# main_v2_0.net
KiCad netlist of a schematic drawn in EAGLE
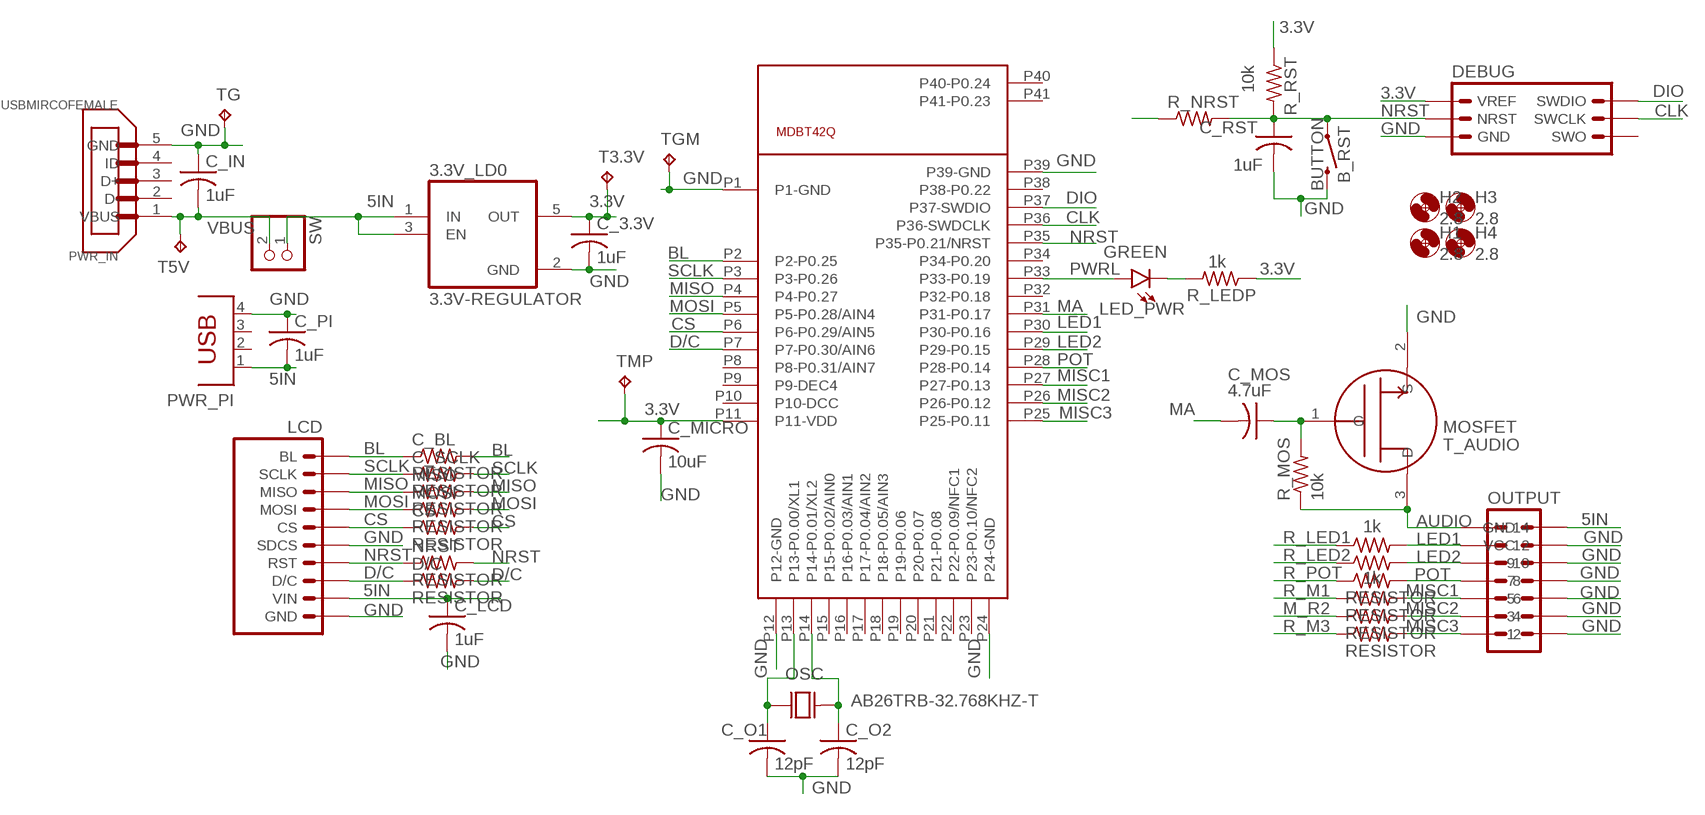
[diagram p0: schematic, sheet 1]

(export (version "E")
  (design (tool "Eeschema 10.0.6"))
  (components
    (comp (ref "3.3V_LD0")
      (value "3.3V-REGULATOR")
      (footprint "eagle-import:SOT95P280X145-5N")
      (fields (field (name "MF") "Texas Instruments") (field (name "MP") "TLV75533PDBVR"))
      (libsource (lib "eagle-import") (part "3.3V-REGULATOR"))
    )
    (comp (ref "B_RST")
      (value "BUTTON")
      (footprint "eagle-import:TACTILE_SWITCH_SMD_6.2MM_TALL")
      (libsource (lib "eagle-import") (part "BUTTON"))
    )
    (comp (ref "CS")
      (value "RESISTOR")
      (footprint "eagle-import:R0805")
      (libsource (lib "eagle-import") (part "RESISTOR"))
    )
    (comp (ref "C_3.3V")
      (value "1uF")
      (footprint "eagle-import:C0805")
      (libsource (lib "eagle-import") (part "CAP"))
    )
    (comp (ref "C_BL")
      (value "RESISTOR")
      (footprint "eagle-import:R0805")
      (libsource (lib "eagle-import") (part "RESISTOR"))
    )
    (comp (ref "C_IN")
      (value "1uF")
      (footprint "eagle-import:C0805")
      (libsource (lib "eagle-import") (part "CAP"))
    )
    (comp (ref "C_LCD")
      (value "1uF")
      (footprint "eagle-import:C0805")
      (libsource (lib "eagle-import") (part "CAP"))
    )
    (comp (ref "C_MICRO")
      (value "10uF")
      (footprint "eagle-import:C0805")
      (libsource (lib "eagle-import") (part "CAP"))
    )
    (comp (ref "C_MOS")
      (value "4.7uF")
      (footprint "eagle-import:C0805")
      (libsource (lib "eagle-import") (part "CAP"))
    )
    (comp (ref "C_O1")
      (value "12pF")
      (footprint "eagle-import:C0805")
      (libsource (lib "eagle-import") (part "CAP"))
    )
    (comp (ref "C_O2")
      (value "12pF")
      (footprint "eagle-import:C0805")
      (libsource (lib "eagle-import") (part "CAP"))
    )
    (comp (ref "C_PI")
      (value "1uF")
      (footprint "eagle-import:C0805")
      (libsource (lib "eagle-import") (part "CAP"))
    )
    (comp (ref "C_RST")
      (value "1uF")
      (footprint "eagle-import:C0805")
      (libsource (lib "eagle-import") (part "CAP"))
    )
    (comp (ref "C_SCLK")
      (value "RESISTOR")
      (footprint "eagle-import:R0805")
      (libsource (lib "eagle-import") (part "RESISTOR"))
    )
    (comp (ref "D/C")
      (value "RESISTOR")
      (footprint "eagle-import:R0805")
      (libsource (lib "eagle-import") (part "RESISTOR"))
    )
    (comp (ref "DEBUG")
      (value "DEBUGGER")
      (footprint "eagle-import:MA03-2")
      (libsource (lib "eagle-import") (part "DEBUGGER"))
    )
    (comp (ref "H1")
      (value "2.8")
      (footprint "eagle-import:2,8")
      (libsource (lib "eagle-import") (part "MOUNT-HOLE2.8"))
    )
    (comp (ref "H2")
      (value "2.8")
      (footprint "eagle-import:2,8")
      (libsource (lib "eagle-import") (part "MOUNT-HOLE2.8"))
    )
    (comp (ref "H3")
      (value "2.8")
      (footprint "eagle-import:2,8")
      (libsource (lib "eagle-import") (part "MOUNT-HOLE2.8"))
    )
    (comp (ref "H4")
      (value "2.8")
      (footprint "eagle-import:2,8")
      (libsource (lib "eagle-import") (part "MOUNT-HOLE2.8"))
    )
    (comp (ref "LCD")
      (value "LCDHEADERS")
      (footprint "eagle-import:MA10-1")
      (libsource (lib "eagle-import") (part "LCDHEADERS"))
    )
    (comp (ref "LED_PWR")
      (value "GREEN")
      (footprint "eagle-import:LED-1206")
      (libsource (lib "eagle-import") (part "LED-GREENLILYPAD"))
    )
    (comp (ref "MISO")
      (value "RESISTOR")
      (footprint "eagle-import:R0805")
      (libsource (lib "eagle-import") (part "RESISTOR"))
    )
    (comp (ref "MOSI")
      (value "RESISTOR")
      (footprint "eagle-import:R0805")
      (libsource (lib "eagle-import") (part "RESISTOR"))
    )
    (comp (ref "M_R2")
      (value "RESISTOR")
      (footprint "eagle-import:R0805")
      (libsource (lib "eagle-import") (part "RESISTOR"))
    )
    (comp (ref "NRST")
      (value "RESISTOR")
      (footprint "eagle-import:R0805")
      (libsource (lib "eagle-import") (part "RESISTOR"))
    )
    (comp (ref "OSC")
      (value "AB26TRB-32.768KHZ-T")
      (footprint "eagle-import:XTAL_AB26TRB-32.768KHZ-T")
      (fields (field (name "DIGI-KEY_PART_NUMBER") "535-9033-1-ND") (field (name "MF") "Abracon"))
      (libsource (lib "eagle-import") (part "AB26TRB-32.768KHZ-T"))
    )
    (comp (ref "OUTPUT")
      (value "OUTHEADER")
      (footprint "eagle-import:MA07-2")
      (libsource (lib "eagle-import") (part "OUTHEADER"))
    )
    (comp (ref "PWR_IN")
      (value "USBMIRCOFEMALE")
      (footprint "eagle-import:MOLEX_0473460001")
      (fields (field (name "MF") "Weidmuller") (field (name "MP") "0473460001"))
      (libsource (lib "eagle-import") (part "USBMIRCOFEMALE"))
    )
    (comp (ref "PWR_PI")
      (value "USBCON")
      (footprint "eagle-import:PN87520")
      (libsource (lib "eagle-import") (part "USBCON"))
    )
    (comp (ref "R_LED1")
      (value "1k")
      (footprint "eagle-import:R0805")
      (libsource (lib "eagle-import") (part "RESISTOR"))
    )
    (comp (ref "R_LED2")
      (value "1k")
      (footprint "eagle-import:R0805")
      (libsource (lib "eagle-import") (part "RESISTOR"))
    )
    (comp (ref "R_LEDP")
      (value "1k")
      (footprint "eagle-import:R0805")
      (libsource (lib "eagle-import") (part "RESISTOR"))
    )
    (comp (ref "R_M1")
      (value "RESISTOR")
      (footprint "eagle-import:R0805")
      (libsource (lib "eagle-import") (part "RESISTOR"))
    )
    (comp (ref "R_M3")
      (value "RESISTOR")
      (footprint "eagle-import:R0805")
      (libsource (lib "eagle-import") (part "RESISTOR"))
    )
    (comp (ref "R_MOS")
      (value "10k")
      (footprint "eagle-import:R0805")
      (libsource (lib "eagle-import") (part "RESISTOR"))
    )
    (comp (ref "R_NRST")
      (value "RESISTOR")
      (footprint "eagle-import:R0805")
      (libsource (lib "eagle-import") (part "RESISTOR"))
    )
    (comp (ref "R_POT")
      (value "RESISTOR")
      (footprint "eagle-import:R0805")
      (libsource (lib "eagle-import") (part "RESISTOR"))
    )
    (comp (ref "R_RST")
      (value "10k")
      (footprint "eagle-import:R0805")
      (libsource (lib "eagle-import") (part "RESISTOR"))
    )
    (comp (ref "SW")
      (value "PINHD-1X2")
      (footprint "eagle-import:1X02")
      (libsource (lib "eagle-import") (part "PINHD-1X2"))
    )
    (comp (ref "T3.3V")
      (value "TPTP11SQ")
      (footprint "eagle-import:TP11SQ")
      (libsource (lib "eagle-import") (part "TPTP11SQ"))
    )
    (comp (ref "T5V")
      (value "TPTP11SQ")
      (footprint "eagle-import:TP11SQ")
      (libsource (lib "eagle-import") (part "TPTP11SQ"))
    )
    (comp (ref "TG")
      (value "TPTP11SQ")
      (footprint "eagle-import:TP11SQ")
      (libsource (lib "eagle-import") (part "TPTP11SQ"))
    )
    (comp (ref "TGM")
      (value "TPTP11SQ")
      (footprint "eagle-import:TP11SQ")
      (libsource (lib "eagle-import") (part "TPTP11SQ"))
    )
    (comp (ref "TMP")
      (value "TPTP11SQ")
      (footprint "eagle-import:TP11SQ")
      (libsource (lib "eagle-import") (part "TPTP11SQ"))
    )
    (comp (ref "T_AUDIO")
      (value "MOSFET")
      (footprint "eagle-import:SOT23")
      (libsource (lib "eagle-import") (part "MOSFET"))
    )
    (comp (ref "U$1")
      (value "MDBT42Q")
      (footprint "eagle-import:MDBT40")
      (libsource (lib "eagle-import") (part "MDBT42Q"))
    )
  )
  (nets
    (net (code "1") (name "/3.3V") (class "Default")
      (node (ref "3.3V_LD0") (pin "5") (pinfunction "OUT_5") (pintype "output"))
      (node (ref "C_3.3V") (pin "1") (pinfunction "1_1") (pintype "passive"))
      (node (ref "C_MICRO") (pin "1") (pinfunction "1_1") (pintype "passive"))
      (node (ref "DEBUG") (pin "6") (pinfunction "VREF_6") (pintype "passive"))
      (node (ref "R_LEDP") (pin "1") (pinfunction "1_1") (pintype "passive"))
      (node (ref "R_RST") (pin "1") (pinfunction "1_1") (pintype "passive"))
      (node (ref "T3.3V") (pin "TP") (pinfunction "TP_TP") (pintype "input"))
      (node (ref "TMP") (pin "TP") (pinfunction "TP_TP") (pintype "input"))
      (node (ref "U$1") (pin "P11") (pinfunction "P11-VDD_P11") (pintype "bidirectional"))
    )
    (net (code "2") (name "/5IN") (class "Default")
      (node (ref "3.3V_LD0") (pin "1") (pinfunction "IN_1") (pintype "input"))
      (node (ref "3.3V_LD0") (pin "3") (pinfunction "EN_3") (pintype "input"))
      (node (ref "C_LCD") (pin "1") (pinfunction "1_1") (pintype "passive"))
      (node (ref "C_PI") (pin "2") (pinfunction "2_2") (pintype "passive"))
      (node (ref "LCD") (pin "2") (pinfunction "VIN_2") (pintype "passive"))
      (node (ref "OUTPUT") (pin "13") (pinfunction "GND_13") (pintype "passive"))
      (node (ref "PWR_PI") (pin "1") (pinfunction "1_1") (pintype "passive"))
      (node (ref "SW") (pin "1") (pinfunction "1_1") (pintype "passive"))
    )
    (net (code "3") (name "/AUDIO") (class "Default")
      (node (ref "OUTPUT") (pin "14") (pinfunction "14_14") (pintype "passive"))
      (node (ref "R_MOS") (pin "1") (pinfunction "1_1") (pintype "passive"))
      (node (ref "T_AUDIO") (pin "3") (pinfunction "D_3") (pintype "bidirectional"))
    )
    (net (code "4") (name "/BL") (class "Default")
      (node (ref "C_BL") (pin "1") (pinfunction "1_1") (pintype "passive"))
      (node (ref "C_BL") (pin "2") (pinfunction "2_2") (pintype "passive"))
      (node (ref "LCD") (pin "10") (pinfunction "BL_10") (pintype "passive"))
      (node (ref "U$1") (pin "P2") (pinfunction "P2-P0.25_P2") (pintype "bidirectional"))
    )
    (net (code "5") (name "/CLK") (class "Default")
      (node (ref "DEBUG") (pin "3") (pinfunction "SWCLK_3") (pintype "passive"))
      (node (ref "U$1") (pin "P36") (pinfunction "P36-SWDCLK_P36") (pintype "bidirectional"))
    )
    (net (code "6") (name "/CS") (class "Default")
      (node (ref "CS") (pin "1") (pinfunction "1_1") (pintype "passive"))
      (node (ref "CS") (pin "2") (pinfunction "2_2") (pintype "passive"))
      (node (ref "LCD") (pin "6") (pinfunction "CS_6") (pintype "passive"))
      (node (ref "U$1") (pin "P6") (pinfunction "P6-P0.29/AIN5_P6") (pintype "bidirectional"))
    )
    (net (code "7") (name "/DIO") (class "Default")
      (node (ref "DEBUG") (pin "5") (pinfunction "SWDIO_5") (pintype "passive"))
      (node (ref "U$1") (pin "P37") (pinfunction "P37-SWDIO_P37") (pintype "bidirectional"))
    )
    (net (code "8") (name "/D{slash}C") (class "Default")
      (node (ref "D/C") (pin "1") (pinfunction "1_1") (pintype "passive"))
      (node (ref "D/C") (pin "2") (pinfunction "2_2") (pintype "passive"))
      (node (ref "LCD") (pin "3") (pinfunction "D/C_3") (pintype "passive"))
      (node (ref "U$1") (pin "P7") (pinfunction "P7-P0.30/AIN6_P7") (pintype "bidirectional"))
    )
    (net (code "9") (name "/GND") (class "Default")
      (node (ref "3.3V_LD0") (pin "2") (pinfunction "GND_2") (pintype "power_in"))
      (node (ref "B_RST") (pin "B1") (pinfunction "2_B1") (pintype "passive"))
      (node (ref "B_RST") (pin "B2") (pinfunction "2_B2") (pintype "passive"))
      (node (ref "C_3.3V") (pin "2") (pinfunction "2_2") (pintype "passive"))
      (node (ref "C_IN") (pin "1") (pinfunction "1_1") (pintype "passive"))
      (node (ref "C_LCD") (pin "2") (pinfunction "2_2") (pintype "passive"))
      (node (ref "C_MICRO") (pin "2") (pinfunction "2_2") (pintype "passive"))
      (node (ref "C_O1") (pin "2") (pinfunction "2_2") (pintype "passive"))
      (node (ref "C_O2") (pin "2") (pinfunction "2_2") (pintype "passive"))
      (node (ref "C_PI") (pin "1") (pinfunction "1_1") (pintype "passive"))
      (node (ref "C_RST") (pin "2") (pinfunction "2_2") (pintype "passive"))
      (node (ref "DEBUG") (pin "2") (pinfunction "GND_2") (pintype "passive"))
      (node (ref "LCD") (pin "1") (pinfunction "GND_1") (pintype "passive"))
      (node (ref "LCD") (pin "5") (pinfunction "SDCS_5") (pintype "passive"))
      (node (ref "OUTPUT") (pin "1") (pinfunction "1_1") (pintype "passive"))
      (node (ref "OUTPUT") (pin "11") (pinfunction "VCC_11") (pintype "passive"))
      (node (ref "OUTPUT") (pin "3") (pinfunction "3_3") (pintype "passive"))
      (node (ref "OUTPUT") (pin "5") (pinfunction "5_5") (pintype "passive"))
      (node (ref "OUTPUT") (pin "7") (pinfunction "7_7") (pintype "passive"))
      (node (ref "OUTPUT") (pin "9") (pinfunction "9_9") (pintype "passive"))
      (node (ref "PWR_IN") (pin "5") (pinfunction "GND_5") (pintype "passive"))
      (node (ref "PWR_PI") (pin "4") (pinfunction "4_4") (pintype "passive"))
      (node (ref "TG") (pin "TP") (pinfunction "TP_TP") (pintype "input"))
      (node (ref "TGM") (pin "TP") (pinfunction "TP_TP") (pintype "input"))
      (node (ref "T_AUDIO") (pin "2") (pinfunction "S_2") (pintype "bidirectional"))
      (node (ref "U$1") (pin "P1") (pinfunction "P1-GND_P1") (pintype "bidirectional"))
      (node (ref "U$1") (pin "P12") (pinfunction "P12-GND_P12") (pintype "bidirectional"))
      (node (ref "U$1") (pin "P24") (pinfunction "P24-GND_P24") (pintype "bidirectional"))
      (node (ref "U$1") (pin "P39") (pinfunction "P39-GND_P39") (pintype "bidirectional"))
    )
    (net (code "10") (name "/LED1") (class "Default")
      (node (ref "OUTPUT") (pin "12") (pinfunction "12_12") (pintype "passive"))
      (node (ref "R_LED1") (pin "1") (pinfunction "1_1") (pintype "passive"))
      (node (ref "R_LED1") (pin "2") (pinfunction "2_2") (pintype "passive"))
      (node (ref "U$1") (pin "P30") (pinfunction "P30-P0.16_P30") (pintype "bidirectional"))
    )
    (net (code "11") (name "/LED2") (class "Default")
      (node (ref "OUTPUT") (pin "10") (pinfunction "10_10") (pintype "passive"))
      (node (ref "R_LED2") (pin "1") (pinfunction "1_1") (pintype "passive"))
      (node (ref "R_LED2") (pin "2") (pinfunction "2_2") (pintype "passive"))
      (node (ref "U$1") (pin "P29") (pinfunction "P29-P0.15_P29") (pintype "bidirectional"))
    )
    (net (code "12") (name "/MA") (class "Default")
      (node (ref "C_MOS") (pin "2") (pinfunction "2_2") (pintype "passive"))
      (node (ref "U$1") (pin "P31") (pinfunction "P31-P0.17_P31") (pintype "bidirectional"))
    )
    (net (code "13") (name "/MISC1") (class "Default")
      (node (ref "OUTPUT") (pin "6") (pinfunction "6_6") (pintype "passive"))
      (node (ref "R_M1") (pin "1") (pinfunction "1_1") (pintype "passive"))
      (node (ref "R_M1") (pin "2") (pinfunction "2_2") (pintype "passive"))
      (node (ref "U$1") (pin "P27") (pinfunction "P27-P0.13_P27") (pintype "bidirectional"))
    )
    (net (code "14") (name "/MISC2") (class "Default")
      (node (ref "M_R2") (pin "1") (pinfunction "1_1") (pintype "passive"))
      (node (ref "M_R2") (pin "2") (pinfunction "2_2") (pintype "passive"))
      (node (ref "OUTPUT") (pin "4") (pinfunction "4_4") (pintype "passive"))
      (node (ref "U$1") (pin "P26") (pinfunction "P26-P0.12_P26") (pintype "bidirectional"))
    )
    (net (code "15") (name "/MISC3") (class "Default")
      (node (ref "OUTPUT") (pin "2") (pinfunction "2_2") (pintype "passive"))
      (node (ref "R_M3") (pin "1") (pinfunction "1_1") (pintype "passive"))
      (node (ref "R_M3") (pin "2") (pinfunction "2_2") (pintype "passive"))
      (node (ref "U$1") (pin "P25") (pinfunction "P25-P0.11_P25") (pintype "bidirectional"))
    )
    (net (code "16") (name "/MISO") (class "Default")
      (node (ref "LCD") (pin "8") (pinfunction "MISO_8") (pintype "passive"))
      (node (ref "MISO") (pin "1") (pinfunction "1_1") (pintype "passive"))
      (node (ref "MISO") (pin "2") (pinfunction "2_2") (pintype "passive"))
      (node (ref "U$1") (pin "P4") (pinfunction "P4-P0.27_P4") (pintype "bidirectional"))
    )
    (net (code "17") (name "/MOSI") (class "Default")
      (node (ref "LCD") (pin "7") (pinfunction "MOSI_7") (pintype "passive"))
      (node (ref "MOSI") (pin "1") (pinfunction "1_1") (pintype "passive"))
      (node (ref "MOSI") (pin "2") (pinfunction "2_2") (pintype "passive"))
      (node (ref "U$1") (pin "P5") (pinfunction "P5-P0.28/AIN4_P5") (pintype "bidirectional"))
    )
    (net (code "18") (name "/NRST") (class "Default")
      (node (ref "B_RST") (pin "A1") (pinfunction "1_A1") (pintype "passive"))
      (node (ref "B_RST") (pin "A2") (pinfunction "1_A2") (pintype "passive"))
      (node (ref "C_RST") (pin "1") (pinfunction "1_1") (pintype "passive"))
      (node (ref "DEBUG") (pin "4") (pinfunction "NRST_4") (pintype "passive"))
      (node (ref "LCD") (pin "4") (pinfunction "RST_4") (pintype "passive"))
      (node (ref "NRST") (pin "1") (pinfunction "1_1") (pintype "passive"))
      (node (ref "NRST") (pin "2") (pinfunction "2_2") (pintype "passive"))
      (node (ref "R_NRST") (pin "1") (pinfunction "1_1") (pintype "passive"))
      (node (ref "R_NRST") (pin "2") (pinfunction "2_2") (pintype "passive"))
      (node (ref "R_RST") (pin "2") (pinfunction "2_2") (pintype "passive"))
      (node (ref "U$1") (pin "P35") (pinfunction "P35-P0.21/NRST_P35") (pintype "bidirectional"))
    )
    (net (code "19") (name "/POT") (class "Default")
      (node (ref "OUTPUT") (pin "8") (pinfunction "8_8") (pintype "passive"))
      (node (ref "R_POT") (pin "1") (pinfunction "1_1") (pintype "passive"))
      (node (ref "R_POT") (pin "2") (pinfunction "2_2") (pintype "passive"))
      (node (ref "U$1") (pin "P28") (pinfunction "P28-P0.14_P28") (pintype "bidirectional"))
    )
    (net (code "20") (name "/PWRL") (class "Default")
      (node (ref "LED_PWR") (pin "A") (pinfunction "A_A") (pintype "passive"))
      (node (ref "U$1") (pin "P33") (pinfunction "P33-P0.19_P33") (pintype "bidirectional"))
    )
    (net (code "21") (name "/SCLK") (class "Default")
      (node (ref "C_SCLK") (pin "1") (pinfunction "1_1") (pintype "passive"))
      (node (ref "C_SCLK") (pin "2") (pinfunction "2_2") (pintype "passive"))
      (node (ref "LCD") (pin "9") (pinfunction "SCLK_9") (pintype "passive"))
      (node (ref "U$1") (pin "P3") (pinfunction "P3-P0.26_P3") (pintype "bidirectional"))
    )
    (net (code "22") (name "/VBUS") (class "Default")
      (node (ref "C_IN") (pin "2") (pinfunction "2_2") (pintype "passive"))
      (node (ref "PWR_IN") (pin "1") (pinfunction "VBUS_1") (pintype "power_in"))
      (node (ref "SW") (pin "2") (pinfunction "2_2") (pintype "passive"))
      (node (ref "T5V") (pin "TP") (pinfunction "TP_TP") (pintype "input"))
    )
    (net (code "23") (name "Net-(LED_PWR-PadC)") (class "Default")
      (node (ref "LED_PWR") (pin "C") (pinfunction "C_C") (pintype "passive"))
      (node (ref "R_LEDP") (pin "2") (pinfunction "2_2") (pintype "passive"))
    )
    (net (code "24") (name "Net-(T_AUDIO-G)") (class "Default")
      (node (ref "C_MOS") (pin "1") (pinfunction "1_1") (pintype "passive"))
      (node (ref "R_MOS") (pin "2") (pinfunction "2_2") (pintype "passive"))
      (node (ref "T_AUDIO") (pin "1") (pinfunction "G_1") (pintype "bidirectional"))
    )
    (net (code "25") (name "Net-(U$1-P13-P0.00{slash}XL1)") (class "Default")
      (node (ref "C_O1") (pin "1") (pinfunction "1_1") (pintype "passive"))
      (node (ref "OSC") (pin "1") (pinfunction "1_1") (pintype "passive"))
      (node (ref "U$1") (pin "P13") (pinfunction "P13-P0.00/XL1_P13") (pintype "bidirectional"))
    )
    (net (code "26") (name "Net-(U$1-P14-P0.01{slash}XL2)") (class "Default")
      (node (ref "C_O2") (pin "1") (pinfunction "1_1") (pintype "passive"))
      (node (ref "OSC") (pin "2") (pinfunction "2_2") (pintype "passive"))
      (node (ref "U$1") (pin "P14") (pinfunction "P14-P0.01/XL2_P14") (pintype "bidirectional"))
    )
    (net (code "27") (name "unconnected-(DEBUG-SWO-Pad1)") (class "Default")
      (node (ref "DEBUG") (pin "1") (pinfunction "SWO_1") (pintype "passive"))
    )
    (net (code "28") (name "unconnected-(PWR_IN-D+-Pad3)") (class "Default")
      (node (ref "PWR_IN") (pin "3") (pinfunction "D+_3") (pintype "bidirectional"))
    )
    (net (code "29") (name "unconnected-(PWR_IN-D--Pad2)") (class "Default")
      (node (ref "PWR_IN") (pin "2") (pinfunction "D-_2") (pintype "bidirectional"))
    )
    (net (code "30") (name "unconnected-(PWR_IN-ID-Pad4)") (class "Default")
      (node (ref "PWR_IN") (pin "4") (pinfunction "ID_4") (pintype "bidirectional"))
    )
    (net (code "31") (name "unconnected-(PWR_PI-Pad2)") (class "Default")
      (node (ref "PWR_PI") (pin "2") (pinfunction "2_2") (pintype "passive"))
    )
    (net (code "32") (name "unconnected-(PWR_PI-Pad3)") (class "Default")
      (node (ref "PWR_PI") (pin "3") (pinfunction "3_3") (pintype "passive"))
    )
    (net (code "33") (name "unconnected-(U$1-P8-P0.31{slash}AIN7-PadP8)") (class "Default")
      (node (ref "U$1") (pin "P8") (pinfunction "P8-P0.31/AIN7_P8") (pintype "bidirectional"))
    )
    (net (code "34") (name "unconnected-(U$1-P9-DEC4-PadP9)") (class "Default")
      (node (ref "U$1") (pin "P9") (pinfunction "P9-DEC4_P9") (pintype "bidirectional"))
    )
    (net (code "35") (name "unconnected-(U$1-P10-DCC-PadP10)") (class "Default")
      (node (ref "U$1") (pin "P10") (pinfunction "P10-DCC_P10") (pintype "bidirectional"))
    )
    (net (code "36") (name "unconnected-(U$1-P15-P0.02{slash}AIN0-PadP15)") (class "Default")
      (node (ref "U$1") (pin "P15") (pinfunction "P15-P0.02/AIN0_P15") (pintype "bidirectional"))
    )
    (net (code "37") (name "unconnected-(U$1-P16-P0.03{slash}AIN1-PadP16)") (class "Default")
      (node (ref "U$1") (pin "P16") (pinfunction "P16-P0.03/AIN1_P16") (pintype "bidirectional"))
    )
    (net (code "38") (name "unconnected-(U$1-P17-P0.04{slash}AIN2-PadP17)") (class "Default")
      (node (ref "U$1") (pin "P17") (pinfunction "P17-P0.04/AIN2_P17") (pintype "bidirectional"))
    )
    (net (code "39") (name "unconnected-(U$1-P18-P0.05{slash}AIN3-PadP18)") (class "Default")
      (node (ref "U$1") (pin "P18") (pinfunction "P18-P0.05/AIN3_P18") (pintype "bidirectional"))
    )
    (net (code "40") (name "unconnected-(U$1-P19-P0.06-PadP19)") (class "Default")
      (node (ref "U$1") (pin "P19") (pinfunction "P19-P0.06_P19") (pintype "bidirectional"))
    )
    (net (code "41") (name "unconnected-(U$1-P20-P0.07-PadP20)") (class "Default")
      (node (ref "U$1") (pin "P20") (pinfunction "P20-P0.07_P20") (pintype "bidirectional"))
    )
    (net (code "42") (name "unconnected-(U$1-P21-P0.08-PadP21)") (class "Default")
      (node (ref "U$1") (pin "P21") (pinfunction "P21-P0.08_P21") (pintype "bidirectional"))
    )
    (net (code "43") (name "unconnected-(U$1-P22-P0.09{slash}NFC1-PadP22)") (class "Default")
      (node (ref "U$1") (pin "P22") (pinfunction "P22-P0.09/NFC1_P22") (pintype "bidirectional"))
    )
    (net (code "44") (name "unconnected-(U$1-P23-P0.10{slash}NFC2-PadP23)") (class "Default")
      (node (ref "U$1") (pin "P23") (pinfunction "P23-P0.10/NFC2_P23") (pintype "bidirectional"))
    )
    (net (code "45") (name "unconnected-(U$1-P32-P0.18-PadP32)") (class "Default")
      (node (ref "U$1") (pin "P32") (pinfunction "P32-P0.18_P32") (pintype "bidirectional"))
    )
    (net (code "46") (name "unconnected-(U$1-P34-P0.20-PadP34)") (class "Default")
      (node (ref "U$1") (pin "P34") (pinfunction "P34-P0.20_P34") (pintype "bidirectional"))
    )
    (net (code "47") (name "unconnected-(U$1-P38-P0.22-PadP38)") (class "Default")
      (node (ref "U$1") (pin "P38") (pinfunction "P38-P0.22_P38") (pintype "bidirectional"))
    )
    (net (code "48") (name "unconnected-(U$1-P40-P0.24-PadP40)") (class "Default")
      (node (ref "U$1") (pin "P40") (pinfunction "P40-P0.24_P40") (pintype "bidirectional"))
    )
    (net (code "49") (name "unconnected-(U$1-P41-P0.23-PadP41)") (class "Default")
      (node (ref "U$1") (pin "P41") (pinfunction "P41-P0.23_P41") (pintype "bidirectional"))
    )
  )
)
